# Single-ADC_ADS1252U.net
KiCad netlist of a schematic drawn in Altium Designer
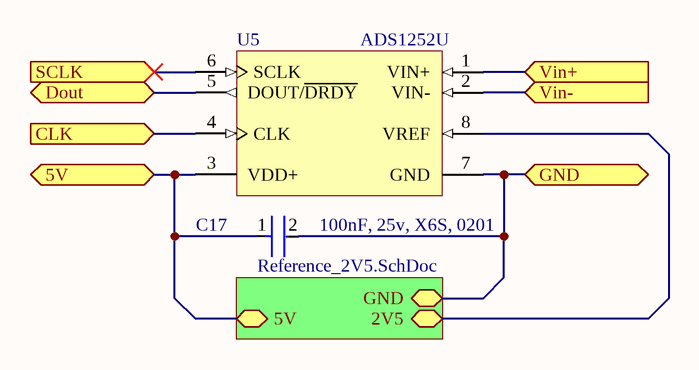
[diagram p0: Single-ADC_ADS1252U.SchDoc]

(export (version "E")
  (design (tool "Eeschema 10.0.6"))
  (components
    (comp (ref "C17")
      (value "100nF, 25v, X6S, 0201")
      (footprint "FP-GRM033-0_03-IPC_B")
      (description "Chip Multilayer Ceramic Capacitors for General Purpose, 0201, 0.10uF, X6S, 22%, 10%, 25V")
      (fields (field (name "TOLERANCE") "10%"))
      (libsource (lib "Altium Content Vault") (part "b4654b650e69147ec39a6b967a45e02"))
    )
    (comp (ref "U5")
      (value "ADS1252U")
      (footprint "TI-D8_M")
      (description "ResolutionPlus 24-Bit, 40 kHz ADC, -40 to 85 degC, 8-pin SOIC (D8), Green (RoHS & no Sb/Br)")
      (fields (field (name "MANUFACTURER") "Texas Instruments"))
      (libsource (lib "Altium Content Vault") (part "TI-ADS125XD8"))
    )
  )
  (nets
    (net (code "1") (name "/2V5") (class "Default")
      (node (ref "U5") (pin "8") (pinfunction "VREF_8") (pintype "input"))
    )
    (net (code "2") (name "/5V") (class "Default")
      (node (ref "C17") (pin "1") (pinfunction "1_1") (pintype "passive"))
      (node (ref "U5") (pin "3") (pinfunction "VDD+_3") (pintype "power_in"))
    )
    (net (code "3") (name "/CLK") (class "Default")
      (node (ref "U5") (pin "4") (pinfunction "CLK_4") (pintype "input"))
    )
    (net (code "4") (name "/Dout") (class "Default")
      (node (ref "U5") (pin "5") (pinfunction "DOUT/~{DRDY}_5") (pintype "output"))
    )
    (net (code "5") (name "/GND") (class "Default")
      (node (ref "C17") (pin "2") (pinfunction "2_2") (pintype "passive"))
      (node (ref "U5") (pin "7") (pinfunction "GND_7") (pintype "power_in"))
    )
    (net (code "6") (name "/SCLK") (class "Default")
      (node (ref "U5") (pin "6") (pinfunction "SCLK_6") (pintype "input+no_connect"))
    )
    (net (code "7") (name "/Vin+") (class "Default")
      (node (ref "U5") (pin "1") (pinfunction "VIN+_1") (pintype "input"))
    )
    (net (code "8") (name "/Vin-") (class "Default")
      (node (ref "U5") (pin "2") (pinfunction "VIN-_2") (pintype "input"))
    )
  )
)
